# Motor_CC.net
KiCad netlist of a schematic drawn in EAGLE
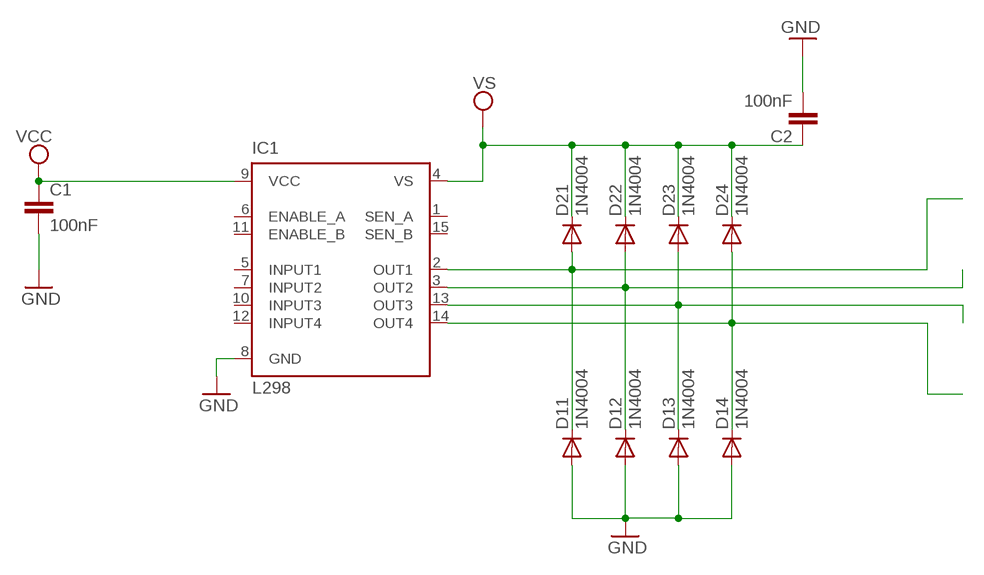
[diagram p0: schematic, sheet 1]

(export (version "E")
  (design (tool "Eeschema 10.0.6"))
  (components
    (comp (ref "C1")
      (value "100nF")
      (footprint "eagle-import:C025-030X050")
      (libsource (lib "eagle-import") (part "C-EU025-030X050"))
    )
    (comp (ref "C2")
      (value "100nF")
      (footprint "eagle-import:C025-030X050")
      (libsource (lib "eagle-import") (part "C-EU025-030X050"))
    )
    (comp (ref "D11")
      (value "1N4004")
      (footprint "eagle-import:DO41-10")
      (libsource (lib "eagle-import") (part "1N4004"))
    )
    (comp (ref "D12")
      (value "1N4004")
      (footprint "eagle-import:DO41-10")
      (libsource (lib "eagle-import") (part "1N4004"))
    )
    (comp (ref "D13")
      (value "1N4004")
      (footprint "eagle-import:DO41-10")
      (libsource (lib "eagle-import") (part "1N4004"))
    )
    (comp (ref "D14")
      (value "1N4004")
      (footprint "eagle-import:DO41-10")
      (libsource (lib "eagle-import") (part "1N4004"))
    )
    (comp (ref "D21")
      (value "1N4004")
      (footprint "eagle-import:DO41-10")
      (libsource (lib "eagle-import") (part "1N4004"))
    )
    (comp (ref "D22")
      (value "1N4004")
      (footprint "eagle-import:DO41-10")
      (libsource (lib "eagle-import") (part "1N4004"))
    )
    (comp (ref "D23")
      (value "1N4004")
      (footprint "eagle-import:DO41-10")
      (libsource (lib "eagle-import") (part "1N4004"))
    )
    (comp (ref "D24")
      (value "1N4004")
      (footprint "eagle-import:DO41-10")
      (libsource (lib "eagle-import") (part "1N4004"))
    )
    (comp (ref "IC1")
      (value "L298")
      (footprint "eagle-import:MULTIWATT-15")
      (fields (field (name "MPN") "L298N"))
      (libsource (lib "eagle-import") (part "L298"))
    )
  )
  (nets
    (net (code "1") (name "GND") (class "Default")
      (node (ref "C1") (pin "2") (pinfunction "2_2") (pintype "passive"))
      (node (ref "C2") (pin "2") (pinfunction "2_2") (pintype "passive"))
      (node (ref "D11") (pin "A") (pinfunction "A_A") (pintype "passive"))
      (node (ref "D12") (pin "A") (pinfunction "A_A") (pintype "passive"))
      (node (ref "D13") (pin "A") (pinfunction "A_A") (pintype "passive"))
      (node (ref "D14") (pin "A") (pinfunction "A_A") (pintype "passive"))
      (node (ref "IC1") (pin "8") (pinfunction "GND_8") (pintype "power_in"))
    )
    (net (code "2") (name "Net-(IC1-OUT1)") (class "Default")
      (node (ref "D11") (pin "C") (pinfunction "C_C") (pintype "passive"))
      (node (ref "D21") (pin "A") (pinfunction "A_A") (pintype "passive"))
      (node (ref "IC1") (pin "2") (pinfunction "OUT1_2") (pintype "output"))
    )
    (net (code "3") (name "Net-(IC1-OUT2)") (class "Default")
      (node (ref "D12") (pin "C") (pinfunction "C_C") (pintype "passive"))
      (node (ref "D22") (pin "A") (pinfunction "A_A") (pintype "passive"))
      (node (ref "IC1") (pin "3") (pinfunction "OUT2_3") (pintype "output"))
    )
    (net (code "4") (name "Net-(IC1-OUT3)") (class "Default")
      (node (ref "D13") (pin "C") (pinfunction "C_C") (pintype "passive"))
      (node (ref "D23") (pin "A") (pinfunction "A_A") (pintype "passive"))
      (node (ref "IC1") (pin "13") (pinfunction "OUT3_13") (pintype "output"))
    )
    (net (code "5") (name "Net-(IC1-OUT4)") (class "Default")
      (node (ref "D14") (pin "C") (pinfunction "C_C") (pintype "passive"))
      (node (ref "D24") (pin "A") (pinfunction "A_A") (pintype "passive"))
      (node (ref "IC1") (pin "14") (pinfunction "OUT4_14") (pintype "output"))
    )
    (net (code "6") (name "VCC") (class "Default")
      (node (ref "C1") (pin "1") (pinfunction "1_1") (pintype "passive"))
      (node (ref "C2") (pin "1") (pinfunction "1_1") (pintype "passive"))
      (node (ref "D21") (pin "C") (pinfunction "C_C") (pintype "passive"))
      (node (ref "D22") (pin "C") (pinfunction "C_C") (pintype "passive"))
      (node (ref "D23") (pin "C") (pinfunction "C_C") (pintype "passive"))
      (node (ref "D24") (pin "C") (pinfunction "C_C") (pintype "passive"))
      (node (ref "IC1") (pin "4") (pinfunction "VS_4") (pintype "power_in"))
      (node (ref "IC1") (pin "9") (pinfunction "VCC_9") (pintype "power_in"))
    )
    (net (code "7") (name "unconnected-(IC1-ENABLE_A-Pad6)") (class "Default")
      (node (ref "IC1") (pin "6") (pinfunction "ENABLE_A_6") (pintype "input"))
    )
    (net (code "8") (name "unconnected-(IC1-ENABLE_B-Pad11)") (class "Default")
      (node (ref "IC1") (pin "11") (pinfunction "ENABLE_B_11") (pintype "input"))
    )
    (net (code "9") (name "unconnected-(IC1-INPUT1-Pad5)") (class "Default")
      (node (ref "IC1") (pin "5") (pinfunction "INPUT1_5") (pintype "input"))
    )
    (net (code "10") (name "unconnected-(IC1-INPUT2-Pad7)") (class "Default")
      (node (ref "IC1") (pin "7") (pinfunction "INPUT2_7") (pintype "input"))
    )
    (net (code "11") (name "unconnected-(IC1-INPUT3-Pad10)") (class "Default")
      (node (ref "IC1") (pin "10") (pinfunction "INPUT3_10") (pintype "input"))
    )
    (net (code "12") (name "unconnected-(IC1-INPUT4-Pad12)") (class "Default")
      (node (ref "IC1") (pin "12") (pinfunction "INPUT4_12") (pintype "input"))
    )
    (net (code "13") (name "unconnected-(IC1-SEN_A-Pad1)") (class "Default")
      (node (ref "IC1") (pin "1") (pinfunction "SEN_A_1") (pintype "input"))
    )
    (net (code "14") (name "unconnected-(IC1-SEN_B-Pad15)") (class "Default")
      (node (ref "IC1") (pin "15") (pinfunction "SEN_B_15") (pintype "input"))
    )
  )
)
